# gesture_control_robot_tx.net
KiCad netlist of a schematic drawn in EAGLE
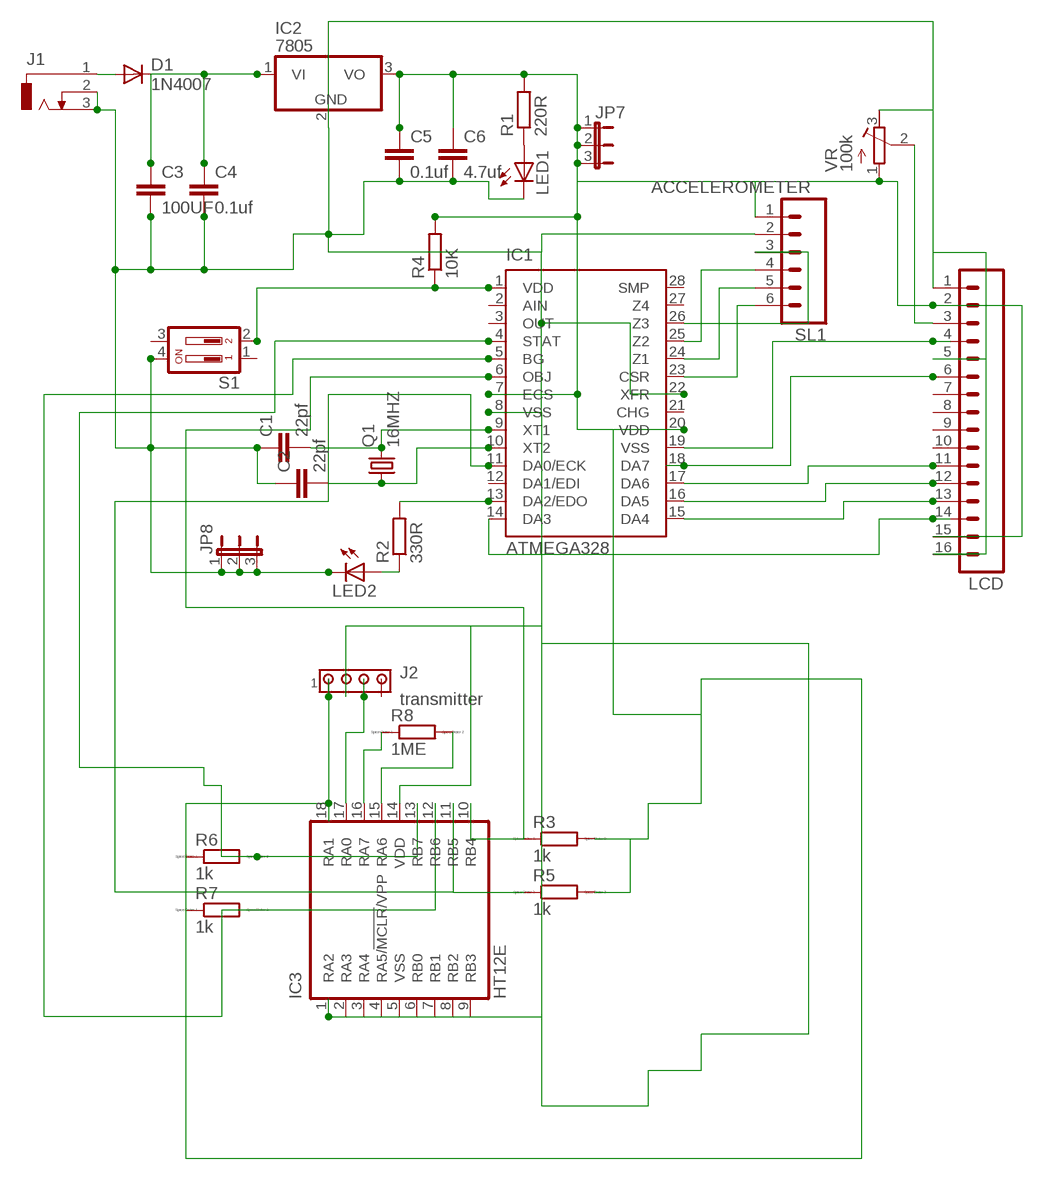
[diagram p0: schematic, sheet 1]

(export (version "E")
  (design (tool "Eeschema 10.0.6"))
  (components
    (comp (ref "C1")
      (value "22pf")
      (footprint "eagle-import:C2.5-2")
      (libsource (lib "eagle-import") (part "C2.5/2"))
    )
    (comp (ref "C2")
      (value "22pf")
      (footprint "eagle-import:C2.5-2")
      (libsource (lib "eagle-import") (part "C2.5/2"))
    )
    (comp (ref "C3")
      (value "100UF")
      (footprint "eagle-import:C2.5-2")
      (libsource (lib "eagle-import") (part "C2.5/2"))
    )
    (comp (ref "C4")
      (value "0.1uf")
      (footprint "eagle-import:C2.5-2")
      (libsource (lib "eagle-import") (part "C2.5/2"))
    )
    (comp (ref "C5")
      (value "0.1uf")
      (footprint "eagle-import:C2.5-2")
      (libsource (lib "eagle-import") (part "C2.5/2"))
    )
    (comp (ref "C6")
      (value "4.7uf")
      (footprint "eagle-import:C2.5-2")
      (libsource (lib "eagle-import") (part "C2.5/2"))
    )
    (comp (ref "D1")
      (value "1N4007")
      (footprint "eagle-import:DO41-10")
      (libsource (lib "eagle-import") (part "1N4004"))
    )
    (comp (ref "IC1")
      (value "ATMEGA328")
      (footprint "eagle-import:DIL28-3")
      (libsource (lib "eagle-import") (part "QT9701BD"))
    )
    (comp (ref "IC2")
      (value "7805")
      (footprint "eagle-import:TO220V")
      (libsource (lib "eagle-import") (part "78TV6"))
    )
    (comp (ref "IC3")
      (value "HT12E")
      (footprint "eagle-import:DIL18")
      (libsource (lib "eagle-import") (part "PIC16F1826/27P"))
    )
    (comp (ref "J1")
      (value "DCJ0303")
      (footprint "eagle-import:DCJ0303")
      (libsource (lib "eagle-import") (part "DCJ0303"))
    )
    (comp (ref "J2")
      (value "transmitter")
      (footprint "eagle-import:10X04MTA")
      (libsource (lib "eagle-import") (part "MTA04-100"))
    )
    (comp (ref "JP7")
      (value "JP2E")
      (footprint "eagle-import:JP2")
      (libsource (lib "eagle-import") (part "JP2E"))
    )
    (comp (ref "JP8")
      (value "JP2E")
      (footprint "eagle-import:JP2")
      (libsource (lib "eagle-import") (part "JP2E"))
    )
    (comp (ref "LCD")
      (value "M16")
      (footprint "eagle-import:16P")
      (libsource (lib "eagle-import") (part "M16"))
    )
    (comp (ref "LED1")
      (value "LED3MM")
      (footprint "eagle-import:LED3MM")
      (libsource (lib "eagle-import") (part "LED3MM"))
    )
    (comp (ref "LED2")
      (value "LED3MM")
      (footprint "eagle-import:LED3MM")
      (libsource (lib "eagle-import") (part "LED3MM"))
    )
    (comp (ref "Q1")
      (value "16MHZ")
      (footprint "eagle-import:HC49_S")
      (libsource (lib "eagle-import") (part "CRYSTALHC49S"))
    )
    (comp (ref "R1")
      (value "220R")
      (footprint "eagle-import:0207_10")
      (libsource (lib "eagle-import") (part "R-EU_0207/10"))
    )
    (comp (ref "R2")
      (value "330R")
      (footprint "eagle-import:0207_10")
      (libsource (lib "eagle-import") (part "R-EU_0207/10"))
    )
    (comp (ref "R3")
      (value "1k")
      (footprint "eagle-import:0204_7")
      (libsource (lib "eagle-import") (part "R0204/7"))
    )
    (comp (ref "R4")
      (value "10K")
      (footprint "eagle-import:0207_10")
      (libsource (lib "eagle-import") (part "R-EU_0207/10"))
    )
    (comp (ref "R5")
      (value "1k")
      (footprint "eagle-import:0204_7")
      (libsource (lib "eagle-import") (part "R0204/7"))
    )
    (comp (ref "R6")
      (value "1k")
      (footprint "eagle-import:0204_7")
      (libsource (lib "eagle-import") (part "R0204/7"))
    )
    (comp (ref "R7")
      (value "1k")
      (footprint "eagle-import:0204_7")
      (libsource (lib "eagle-import") (part "R0204/7"))
    )
    (comp (ref "R8")
      (value "1ME")
      (footprint "eagle-import:0204_7")
      (libsource (lib "eagle-import") (part "R0204/7"))
    )
    (comp (ref "S1")
      (value "DP02")
      (footprint "eagle-import:DP-02")
      (fields (field (name "MPN") "MCDP02"))
      (libsource (lib "eagle-import") (part "DP02"))
    )
    (comp (ref "SL1")
      (value "ACCELEROMETER")
      (footprint "eagle-import:06P")
      (libsource (lib "eagle-import") (part "M06"))
    )
    (comp (ref "VR")
      (value "100k")
      (footprint "eagle-import:RTRIM64P")
      (libsource (lib "eagle-import") (part "R-TRIMM64P"))
    )
  )
  (nets
    (net (code "1") (name "Net-(D1-PadA)") (class "Default")
      (node (ref "D1") (pin "A") (pinfunction "A_A") (pintype "passive"))
      (node (ref "J1") (pin "1") (pinfunction "1_1") (pintype "passive"))
    )
    (net (code "2") (name "Net-(IC1-BG)") (class "Default")
      (node (ref "IC1") (pin "5") (pinfunction "BG_5") (pintype "input"))
      (node (ref "IC3") (pin "12") (pinfunction "RB6_12") (pintype "bidirectional"))
      (node (ref "R7") (pin "2") (pinfunction "2_2") (pintype "passive"))
    )
    (net (code "3") (name "Net-(IC1-CSR)") (class "Default")
      (node (ref "IC1") (pin "23") (pinfunction "CSR_23") (pintype "output"))
      (node (ref "SL1") (pin "6") (pinfunction "6_6") (pintype "passive"))
    )
    (net (code "4") (name "Net-(IC1-DA0{slash}ECK)") (class "Default")
      (node (ref "IC1") (pin "11") (pinfunction "DA0/ECK_11") (pintype "output"))
      (node (ref "IC3") (pin "11") (pinfunction "RB5_11") (pintype "bidirectional"))
      (node (ref "R5") (pin "1") (pinfunction "1_1") (pintype "passive"))
    )
    (net (code "5") (name "Net-(IC1-DA2{slash}EDO)") (class "Default")
      (node (ref "IC1") (pin "13") (pinfunction "DA2/EDO_13") (pintype "output"))
      (node (ref "R2") (pin "2") (pinfunction "2_2") (pintype "passive"))
    )
    (net (code "6") (name "Net-(IC1-DA3)") (class "Default")
      (node (ref "IC1") (pin "14") (pinfunction "DA3_14") (pintype "output"))
      (node (ref "LCD") (pin "14") (pinfunction "14_14") (pintype "passive"))
    )
    (net (code "7") (name "Net-(IC1-DA4)") (class "Default")
      (node (ref "IC1") (pin "15") (pinfunction "DA4_15") (pintype "output"))
      (node (ref "LCD") (pin "13") (pinfunction "13_13") (pintype "passive"))
    )
    (net (code "8") (name "Net-(IC1-DA5)") (class "Default")
      (node (ref "IC1") (pin "16") (pinfunction "DA5_16") (pintype "output"))
      (node (ref "LCD") (pin "12") (pinfunction "12_12") (pintype "passive"))
    )
    (net (code "9") (name "Net-(IC1-DA6)") (class "Default")
      (node (ref "IC1") (pin "17") (pinfunction "DA6_17") (pintype "output"))
      (node (ref "LCD") (pin "11") (pinfunction "11_11") (pintype "passive"))
    )
    (net (code "10") (name "Net-(IC1-DA7)") (class "Default")
      (node (ref "IC1") (pin "18") (pinfunction "DA7_18") (pintype "output"))
      (node (ref "LCD") (pin "6") (pinfunction "6_6") (pintype "passive"))
    )
    (net (code "11") (name "Net-(IC1-ECS)") (class "Default")
      (node (ref "C5") (pin "1") (pinfunction "1_1") (pintype "passive"))
      (node (ref "C6") (pin "1") (pinfunction "1_1") (pintype "passive"))
      (node (ref "IC1") (pin "20") (pinfunction "VDD_20") (pintype "input"))
      (node (ref "IC1") (pin "7") (pinfunction "ECS_7") (pintype "output"))
      (node (ref "IC2") (pin "3") (pinfunction "VO_3") (pintype "passive"))
      (node (ref "IC3") (pin "18") (pinfunction "RA1_18") (pintype "bidirectional"))
      (node (ref "J2") (pin "1") (pinfunction "1_1") (pintype "passive"))
      (node (ref "JP7") (pin "1") (pinfunction "1_1") (pintype "passive"))
      (node (ref "JP7") (pin "2") (pinfunction "2_2") (pintype "passive"))
      (node (ref "JP7") (pin "3") (pinfunction "3_3") (pintype "passive"))
      (node (ref "LCD") (pin "15") (pinfunction "15_15") (pintype "passive"))
      (node (ref "LCD") (pin "2") (pinfunction "2_2") (pintype "passive"))
      (node (ref "R1") (pin "2") (pinfunction "2_2") (pintype "passive"))
      (node (ref "R3") (pin "2") (pinfunction "2_2") (pintype "passive"))
      (node (ref "R4") (pin "2") (pinfunction "2_2") (pintype "passive"))
      (node (ref "R5") (pin "2") (pinfunction "2_2") (pintype "passive"))
      (node (ref "R6") (pin "1") (pinfunction "1_1") (pintype "passive"))
      (node (ref "R7") (pin "1") (pinfunction "1_1") (pintype "passive"))
      (node (ref "SL1") (pin "1") (pinfunction "1_1") (pintype "passive"))
      (node (ref "VR") (pin "1") (pinfunction "E_1") (pintype "passive"))
    )
    (net (code "12") (name "Net-(IC1-OBJ)") (class "Default")
      (node (ref "IC1") (pin "6") (pinfunction "OBJ_6") (pintype "input"))
      (node (ref "IC3") (pin "10") (pinfunction "RB4_10") (pintype "bidirectional"))
      (node (ref "R3") (pin "1") (pinfunction "1_1") (pintype "passive"))
    )
    (net (code "13") (name "Net-(IC1-STAT)") (class "Default")
      (node (ref "IC1") (pin "4") (pinfunction "STAT_4") (pintype "output"))
      (node (ref "IC3") (pin "13") (pinfunction "RB7_13") (pintype "bidirectional"))
      (node (ref "R6") (pin "2") (pinfunction "2_2") (pintype "passive"))
    )
    (net (code "14") (name "Net-(IC1-VDD-Pad1)") (class "Default")
      (node (ref "IC1") (pin "1") (pinfunction "VDD_1") (pintype "input"))
      (node (ref "R4") (pin "1") (pinfunction "1_1") (pintype "passive"))
      (node (ref "S1") (pin "2") (pinfunction "2_2") (pintype "passive"))
    )
    (net (code "15") (name "Net-(IC1-VSS-Pad19)") (class "Default")
      (node (ref "IC1") (pin "19") (pinfunction "VSS_19") (pintype "input"))
      (node (ref "LCD") (pin "4") (pinfunction "4_4") (pintype "passive"))
    )
    (net (code "16") (name "Net-(IC1-XFR)") (class "Default")
      (node (ref "C1") (pin "1") (pinfunction "1_1") (pintype "passive"))
      (node (ref "C2") (pin "1") (pinfunction "1_1") (pintype "passive"))
      (node (ref "C3") (pin "2") (pinfunction "2_2") (pintype "passive"))
      (node (ref "C4") (pin "2") (pinfunction "2_2") (pintype "passive"))
      (node (ref "C5") (pin "2") (pinfunction "2_2") (pintype "passive"))
      (node (ref "C6") (pin "2") (pinfunction "2_2") (pintype "passive"))
      (node (ref "IC1") (pin "22") (pinfunction "XFR_22") (pintype "output"))
      (node (ref "IC1") (pin "8") (pinfunction "VSS_8") (pintype "input"))
      (node (ref "IC2") (pin "2") (pinfunction "GND_2") (pintype "passive"))
      (node (ref "IC3") (pin "1") (pinfunction "RA2_1") (pintype "bidirectional"))
      (node (ref "IC3") (pin "14") (pinfunction "VDD_14") (pintype "power_in"))
      (node (ref "IC3") (pin "2") (pinfunction "RA3_2") (pintype "bidirectional"))
      (node (ref "IC3") (pin "3") (pinfunction "RA4_3") (pintype "bidirectional"))
      (node (ref "IC3") (pin "4") (pinfunction "RA5/~{MCLR}/VPP_4") (pintype "bidirectional"))
      (node (ref "IC3") (pin "5") (pinfunction "VSS_5") (pintype "power_in"))
      (node (ref "IC3") (pin "6") (pinfunction "RB0_6") (pintype "bidirectional"))
      (node (ref "IC3") (pin "7") (pinfunction "RB1_7") (pintype "bidirectional"))
      (node (ref "IC3") (pin "8") (pinfunction "RB2_8") (pintype "bidirectional"))
      (node (ref "IC3") (pin "9") (pinfunction "RB3_9") (pintype "bidirectional"))
      (node (ref "J1") (pin "2") (pinfunction "2_2") (pintype "passive"))
      (node (ref "J1") (pin "3") (pinfunction "3_3") (pintype "passive"))
      (node (ref "J2") (pin "2") (pinfunction "2_2") (pintype "passive"))
      (node (ref "JP8") (pin "1") (pinfunction "1_1") (pintype "passive"))
      (node (ref "JP8") (pin "2") (pinfunction "2_2") (pintype "passive"))
      (node (ref "JP8") (pin "3") (pinfunction "3_3") (pintype "passive"))
      (node (ref "LCD") (pin "1") (pinfunction "1_1") (pintype "passive"))
      (node (ref "LCD") (pin "16") (pinfunction "16_16") (pintype "passive"))
      (node (ref "LCD") (pin "5") (pinfunction "5_5") (pintype "passive"))
      (node (ref "LED1") (pin "K") (pinfunction "C_K") (pintype "passive"))
      (node (ref "LED2") (pin "K") (pinfunction "C_K") (pintype "passive"))
      (node (ref "S1") (pin "4") (pinfunction "4_4") (pintype "passive"))
      (node (ref "SL1") (pin "2") (pinfunction "2_2") (pintype "passive"))
      (node (ref "VR") (pin "3") (pinfunction "A_3") (pintype "passive"))
    )
    (net (code "17") (name "Net-(IC1-XT1)") (class "Default")
      (node (ref "C1") (pin "2") (pinfunction "2_2") (pintype "passive"))
      (node (ref "IC1") (pin "9") (pinfunction "XT1_9") (pintype "input"))
      (node (ref "Q1") (pin "2") (pinfunction "2_2") (pintype "passive"))
    )
    (net (code "18") (name "Net-(IC1-XT2)") (class "Default")
      (node (ref "C2") (pin "2") (pinfunction "2_2") (pintype "passive"))
      (node (ref "IC1") (pin "10") (pinfunction "XT2_10") (pintype "output"))
      (node (ref "Q1") (pin "1") (pinfunction "1_1") (pintype "passive"))
    )
    (net (code "19") (name "Net-(IC1-Z1)") (class "Default")
      (node (ref "IC1") (pin "24") (pinfunction "Z1_24") (pintype "output"))
      (node (ref "SL1") (pin "5") (pinfunction "5_5") (pintype "passive"))
    )
    (net (code "20") (name "Net-(IC1-Z2)") (class "Default")
      (node (ref "IC1") (pin "25") (pinfunction "Z2_25") (pintype "output"))
      (node (ref "SL1") (pin "4") (pinfunction "4_4") (pintype "passive"))
    )
    (net (code "21") (name "Net-(IC1-Z3)") (class "Default")
      (node (ref "IC1") (pin "26") (pinfunction "Z3_26") (pintype "output"))
      (node (ref "SL1") (pin "3") (pinfunction "3_3") (pintype "passive"))
    )
    (net (code "22") (name "Net-(IC2-VI)") (class "Default")
      (node (ref "C3") (pin "1") (pinfunction "1_1") (pintype "passive"))
      (node (ref "C4") (pin "1") (pinfunction "1_1") (pintype "passive"))
      (node (ref "D1") (pin "C") (pinfunction "C_C") (pintype "passive"))
      (node (ref "IC2") (pin "1") (pinfunction "VI_1") (pintype "input"))
    )
    (net (code "23") (name "Net-(IC3-RA0)") (class "Default")
      (node (ref "IC3") (pin "17") (pinfunction "RA0_17") (pintype "bidirectional"))
      (node (ref "J2") (pin "3") (pinfunction "3_3") (pintype "passive"))
    )
    (net (code "24") (name "Net-(IC3-RA6)") (class "Default")
      (node (ref "IC3") (pin "15") (pinfunction "RA6_15") (pintype "bidirectional"))
      (node (ref "R8") (pin "2") (pinfunction "2_2") (pintype "passive"))
    )
    (net (code "25") (name "Net-(IC3-RA7)") (class "Default")
      (node (ref "IC3") (pin "16") (pinfunction "RA7_16") (pintype "bidirectional"))
      (node (ref "R8") (pin "1") (pinfunction "1_1") (pintype "passive"))
    )
    (net (code "26") (name "Net-(LED1-PadA)") (class "Default")
      (node (ref "LED1") (pin "A") (pinfunction "A_A") (pintype "passive"))
      (node (ref "R1") (pin "1") (pinfunction "1_1") (pintype "passive"))
    )
    (net (code "27") (name "Net-(LED2-PadA)") (class "Default")
      (node (ref "LED2") (pin "A") (pinfunction "A_A") (pintype "passive"))
      (node (ref "R2") (pin "1") (pinfunction "1_1") (pintype "passive"))
    )
    (net (code "28") (name "Net-(VR-S)") (class "Default")
      (node (ref "LCD") (pin "3") (pinfunction "3_3") (pintype "passive"))
      (node (ref "VR") (pin "2") (pinfunction "S_2") (pintype "passive"))
    )
    (net (code "29") (name "unconnected-(IC1-AIN-Pad2)") (class "Default")
      (node (ref "IC1") (pin "2") (pinfunction "AIN_2") (pintype "input"))
    )
    (net (code "30") (name "unconnected-(IC1-CHG-Pad21)") (class "Default")
      (node (ref "IC1") (pin "21") (pinfunction "CHG_21") (pintype "output"))
    )
    (net (code "31") (name "unconnected-(IC1-DA1{slash}EDI-Pad12)") (class "Default")
      (node (ref "IC1") (pin "12") (pinfunction "DA1/EDI_12") (pintype "output"))
    )
    (net (code "32") (name "unconnected-(IC1-OUT-Pad3)") (class "Default")
      (node (ref "IC1") (pin "3") (pinfunction "OUT_3") (pintype "output"))
    )
    (net (code "33") (name "unconnected-(IC1-SMP-Pad28)") (class "Default")
      (node (ref "IC1") (pin "28") (pinfunction "SMP_28") (pintype "output"))
    )
    (net (code "34") (name "unconnected-(IC1-Z4-Pad27)") (class "Default")
      (node (ref "IC1") (pin "27") (pinfunction "Z4_27") (pintype "output"))
    )
    (net (code "35") (name "unconnected-(J2-Pad4)") (class "Default")
      (node (ref "J2") (pin "4") (pinfunction "4_4") (pintype "passive"))
    )
    (net (code "36") (name "unconnected-(LCD-Pad7)") (class "Default")
      (node (ref "LCD") (pin "7") (pinfunction "7_7") (pintype "passive"))
    )
    (net (code "37") (name "unconnected-(LCD-Pad8)") (class "Default")
      (node (ref "LCD") (pin "8") (pinfunction "8_8") (pintype "passive"))
    )
    (net (code "38") (name "unconnected-(LCD-Pad9)") (class "Default")
      (node (ref "LCD") (pin "9") (pinfunction "9_9") (pintype "passive"))
    )
    (net (code "39") (name "unconnected-(LCD-Pad10)") (class "Default")
      (node (ref "LCD") (pin "10") (pinfunction "10_10") (pintype "passive"))
    )
    (net (code "40") (name "unconnected-(S1-Pad1)") (class "Default")
      (node (ref "S1") (pin "1") (pinfunction "1_1") (pintype "passive"))
    )
    (net (code "41") (name "unconnected-(S1-Pad3)") (class "Default")
      (node (ref "S1") (pin "3") (pinfunction "3_3") (pintype "passive"))
    )
  )
)
